# devkit_epet.net
KiCad netlist of a schematic drawn in EAGLE
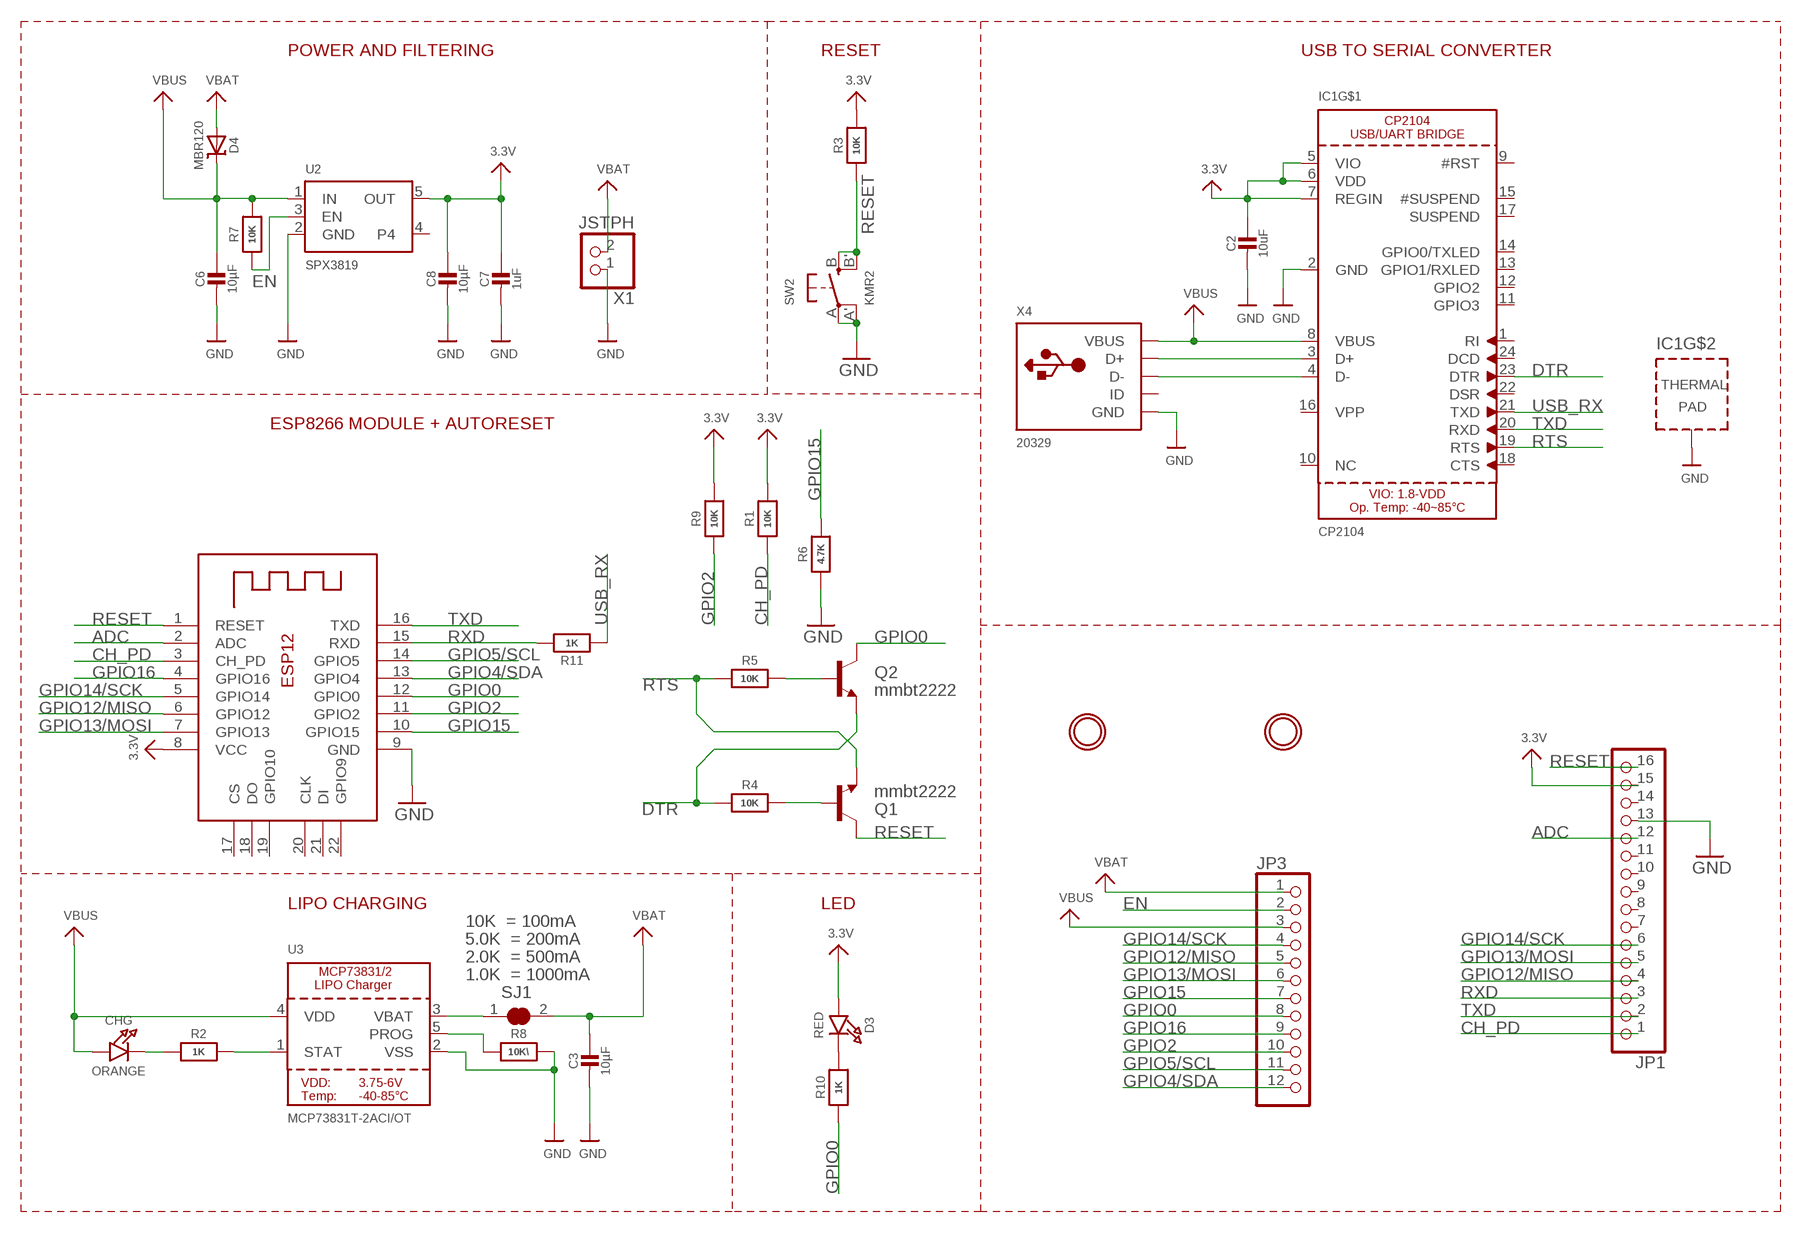
[diagram p0: schematic, sheet 1]

(export (version "E")
  (design (tool "Eeschema 10.0.6"))
  (components
    (comp (ref "C2")
      (value "10uF")
      (footprint "eagle-import:0805-NO")
      (libsource (lib "eagle-import") (part "CAP_CERAMIC0805-NOOUTLINE"))
    )
    (comp (ref "C3")
      (value "10µF")
      (footprint "eagle-import:0805-NO")
      (libsource (lib "eagle-import") (part "CAP_CERAMIC0805-NOOUTLINE"))
    )
    (comp (ref "C6")
      (value "10µF")
      (footprint "eagle-import:0805-NO")
      (libsource (lib "eagle-import") (part "CAP_CERAMIC0805-NOOUTLINE"))
    )
    (comp (ref "C7")
      (value "1uF")
      (footprint "eagle-import:0603-NO")
      (libsource (lib "eagle-import") (part "CAP_CERAMIC0603_NO"))
    )
    (comp (ref "C8")
      (value "10µF")
      (footprint "eagle-import:0805-NO")
      (libsource (lib "eagle-import") (part "CAP_CERAMIC0805-NOOUTLINE"))
    )
    (comp (ref "CHG")
      (value "ORANGE")
      (footprint "eagle-import:CHIPLED_0805_NOOUTLINE")
      (libsource (lib "eagle-import") (part "LED0805_NOOUTLINE"))
    )
    (comp (ref "D3")
      (value "RED")
      (footprint "eagle-import:CHIPLED_0805_NOOUTLINE")
      (libsource (lib "eagle-import") (part "LED0805_NOOUTLINE"))
    )
    (comp (ref "D4")
      (value "MBR120")
      (footprint "eagle-import:SOD-123")
      (libsource (lib "eagle-import") (part "DIODE-SCHOTTKYSOD-123"))
    )
    (comp (ref "IC1")
      (value "CP2104")
      (footprint "eagle-import:QFN24_4MM_SMSC")
      (libsource (lib "eagle-import") (part "CP2104"))
    )
    (comp (ref "JP1")
      (value "HEADER-1X16ROUND")
      (footprint "eagle-import:1X16_ROUND")
      (libsource (lib "eagle-import") (part "HEADER-1X16ROUND"))
    )
    (comp (ref "JP3")
      (value "HEADER-1X12")
      (footprint "eagle-import:1X12_ROUND")
      (libsource (lib "eagle-import") (part "HEADER-1X12"))
    )
    (comp (ref "Q1")
      (value "mmbt2222")
      (footprint "eagle-import:SOT23-3")
      (libsource (lib "eagle-import") (part "TRANSISTOR_NPNSOT23-3"))
    )
    (comp (ref "Q2")
      (value "mmbt2222")
      (footprint "eagle-import:SOT23-3")
      (libsource (lib "eagle-import") (part "TRANSISTOR_NPNSOT23-3"))
    )
    (comp (ref "R1")
      (value "10K")
      (footprint "eagle-import:0603-NO")
      (libsource (lib "eagle-import") (part "RESISTOR_0603_NOOUT"))
    )
    (comp (ref "R2")
      (value "1K")
      (footprint "eagle-import:0603-NO")
      (libsource (lib "eagle-import") (part "RESISTOR_0603_NOOUT"))
    )
    (comp (ref "R3")
      (value "10K")
      (footprint "eagle-import:0603-NO")
      (libsource (lib "eagle-import") (part "RESISTOR_0603_NOOUT"))
    )
    (comp (ref "R4")
      (value "10K")
      (footprint "eagle-import:0603-NO")
      (libsource (lib "eagle-import") (part "RESISTOR_0603_NOOUT"))
    )
    (comp (ref "R5")
      (value "10K")
      (footprint "eagle-import:_0603MP")
      (libsource (lib "eagle-import") (part "RESISTOR_0603MP"))
    )
    (comp (ref "R6")
      (value "4.7K")
      (footprint "eagle-import:0603-NO")
      (libsource (lib "eagle-import") (part "RESISTOR_0603_NOOUT"))
    )
    (comp (ref "R7")
      (value "10K")
      (footprint "eagle-import:0603-NO")
      (libsource (lib "eagle-import") (part "RESISTOR_0603_NOOUT"))
    )
    (comp (ref "R8")
      (value "10K\\")
      (footprint "eagle-import:0603-NO")
      (libsource (lib "eagle-import") (part "RESISTOR_0603_NOOUT"))
    )
    (comp (ref "R9")
      (value "10K")
      (footprint "eagle-import:0603-NO")
      (libsource (lib "eagle-import") (part "RESISTOR_0603_NOOUT"))
    )
    (comp (ref "R10")
      (value "1K")
      (footprint "eagle-import:0603-NO")
      (libsource (lib "eagle-import") (part "RESISTOR_0603_NOOUT"))
    )
    (comp (ref "R11")
      (value "1K")
      (footprint "eagle-import:_0603MP")
      (libsource (lib "eagle-import") (part "RESISTOR_0603MP"))
    )
    (comp (ref "SJ1")
      (value "SOLDERJUMPER_CLOSED")
      (footprint "eagle-import:SOLDERJUMPER_CLOSEDWIRE")
      (libsource (lib "eagle-import") (part "SOLDERJUMPER_CLOSED"))
    )
    (comp (ref "SW2")
      (value "KMR2")
      (footprint "eagle-import:BTN_KMR2_4.6X2.8")
      (libsource (lib "eagle-import") (part "SWITCH_TACT_SMT4.6X2.8"))
    )
    (comp (ref "U$31")
      (value "MOUNTINGHOLE2.5")
      (footprint "eagle-import:MOUNTINGHOLE_2.5_PLATED")
      (libsource (lib "eagle-import") (part "MOUNTINGHOLE2.5"))
    )
    (comp (ref "U$32")
      (value "MOUNTINGHOLE2.5")
      (footprint "eagle-import:MOUNTINGHOLE_2.5_PLATED")
      (libsource (lib "eagle-import") (part "MOUNTINGHOLE2.5"))
    )
    (comp (ref "U2")
      (value "SPX3819")
      (footprint "eagle-import:SOT23-5")
      (libsource (lib "eagle-import") (part "VREG_SOT23-5"))
    )
    (comp (ref "U3")
      (value "MCP73831T-2ACI/OT")
      (footprint "eagle-import:SOT23-5")
      (libsource (lib "eagle-import") (part "MCP73831/2"))
    )
    (comp (ref "X1")
      (value "JSTPH")
      (footprint "eagle-import:JSTPH2")
      (libsource (lib "eagle-import") (part "CON_JST_PH_2PIN"))
    )
    (comp (ref "X2")
      (value "ESP-12")
      (footprint "eagle-import:ESP-12E")
      (libsource (lib "eagle-import") (part "ESP-12E"))
    )
    (comp (ref "X4")
      (value "20329")
      (footprint "eagle-import:4UCONN_20329_V2")
      (libsource (lib "eagle-import") (part "USB_MICRO_20329_V2"))
    )
  )
  (nets
    (net (code "1") (name "/ADC") (class "Default")
      (node (ref "JP1") (pin "12") (pinfunction "12_12") (pintype "passive"))
      (node (ref "X2") (pin "2") (pinfunction "ADC_2") (pintype "passive"))
    )
    (net (code "2") (name "/CH_PD") (class "Default")
      (node (ref "JP1") (pin "1") (pinfunction "1_1") (pintype "passive"))
      (node (ref "R1") (pin "1") (pinfunction "1_1") (pintype "passive"))
      (node (ref "X2") (pin "3") (pinfunction "CH_PD_3") (pintype "input"))
    )
    (net (code "3") (name "/DTR") (class "Default")
      (node (ref "IC1") (pin "23") (pinfunction "DTR_23") (pintype "output"))
      (node (ref "Q2") (pin "2") (pinfunction "E_2") (pintype "passive"))
      (node (ref "R4") (pin "1") (pinfunction "1_1") (pintype "passive"))
    )
    (net (code "4") (name "/EN") (class "Default")
      (node (ref "JP3") (pin "2") (pinfunction "2_2") (pintype "passive"))
      (node (ref "R7") (pin "1") (pinfunction "1_1") (pintype "passive"))
      (node (ref "U2") (pin "3") (pinfunction "EN_3") (pintype "input"))
    )
    (net (code "5") (name "/GPIO0") (class "Default")
      (node (ref "JP3") (pin "8") (pinfunction "8_8") (pintype "passive"))
      (node (ref "Q2") (pin "3") (pinfunction "C_3") (pintype "passive"))
      (node (ref "R10") (pin "1") (pinfunction "1_1") (pintype "passive"))
      (node (ref "X2") (pin "12") (pinfunction "GPIO0_12") (pintype "bidirectional"))
    )
    (net (code "6") (name "/GPIO2") (class "Default")
      (node (ref "JP3") (pin "10") (pinfunction "10_10") (pintype "passive"))
      (node (ref "R9") (pin "1") (pinfunction "1_1") (pintype "passive"))
      (node (ref "X2") (pin "11") (pinfunction "GPIO2_11") (pintype "bidirectional"))
    )
    (net (code "7") (name "/GPIO4{slash}SDA") (class "Default")
      (node (ref "JP3") (pin "12") (pinfunction "12_12") (pintype "passive"))
      (node (ref "X2") (pin "13") (pinfunction "GPIO4_13") (pintype "bidirectional"))
    )
    (net (code "8") (name "/GPIO5{slash}SCL") (class "Default")
      (node (ref "JP3") (pin "11") (pinfunction "11_11") (pintype "passive"))
      (node (ref "X2") (pin "14") (pinfunction "GPIO5_14") (pintype "bidirectional"))
    )
    (net (code "9") (name "/GPIO12{slash}MISO") (class "Default")
      (node (ref "JP1") (pin "4") (pinfunction "4_4") (pintype "passive"))
      (node (ref "JP3") (pin "5") (pinfunction "5_5") (pintype "passive"))
      (node (ref "X2") (pin "6") (pinfunction "GPIO12_6") (pintype "bidirectional"))
    )
    (net (code "10") (name "/GPIO13{slash}MOSI") (class "Default")
      (node (ref "JP1") (pin "5") (pinfunction "5_5") (pintype "passive"))
      (node (ref "JP3") (pin "6") (pinfunction "6_6") (pintype "passive"))
      (node (ref "X2") (pin "7") (pinfunction "GPIO13_7") (pintype "bidirectional"))
    )
    (net (code "11") (name "/GPIO14{slash}SCK") (class "Default")
      (node (ref "JP1") (pin "6") (pinfunction "6_6") (pintype "passive"))
      (node (ref "JP3") (pin "4") (pinfunction "4_4") (pintype "passive"))
      (node (ref "X2") (pin "5") (pinfunction "GPIO14_5") (pintype "bidirectional"))
    )
    (net (code "12") (name "/GPIO15") (class "Default")
      (node (ref "JP3") (pin "7") (pinfunction "7_7") (pintype "passive"))
      (node (ref "R6") (pin "2") (pinfunction "2_2") (pintype "passive"))
      (node (ref "X2") (pin "10") (pinfunction "GPIO15_10") (pintype "bidirectional"))
    )
    (net (code "13") (name "/GPIO16") (class "Default")
      (node (ref "JP3") (pin "9") (pinfunction "9_9") (pintype "passive"))
      (node (ref "X2") (pin "4") (pinfunction "GPIO16_4") (pintype "bidirectional"))
    )
    (net (code "14") (name "/RESET") (class "Default")
      (node (ref "JP1") (pin "16") (pinfunction "16_16") (pintype "passive"))
      (node (ref "Q1") (pin "3") (pinfunction "C_3") (pintype "passive"))
      (node (ref "R3") (pin "1") (pinfunction "1_1") (pintype "passive"))
      (node (ref "SW2") (pin "B") (pinfunction "S_B") (pintype "passive"))
      (node (ref "SW2") (pin "B'") (pinfunction "S1_B'") (pintype "passive"))
      (node (ref "X2") (pin "1") (pinfunction "RESET_1") (pintype "input"))
    )
    (net (code "15") (name "/RTS") (class "Default")
      (node (ref "IC1") (pin "19") (pinfunction "RTS_19") (pintype "output"))
      (node (ref "Q1") (pin "2") (pinfunction "E_2") (pintype "passive"))
      (node (ref "R5") (pin "1") (pinfunction "1_1") (pintype "passive"))
    )
    (net (code "16") (name "/RXD") (class "Default")
      (node (ref "JP1") (pin "3") (pinfunction "3_3") (pintype "passive"))
      (node (ref "R11") (pin "2") (pinfunction "2_2") (pintype "passive"))
      (node (ref "X2") (pin "15") (pinfunction "RXD_15") (pintype "input"))
    )
    (net (code "17") (name "/TXD") (class "Default")
      (node (ref "IC1") (pin "20") (pinfunction "RXD_20") (pintype "input"))
      (node (ref "JP1") (pin "2") (pinfunction "2_2") (pintype "passive"))
      (node (ref "X2") (pin "16") (pinfunction "TXD_16") (pintype "output"))
    )
    (net (code "18") (name "/USB_RX") (class "Default")
      (node (ref "IC1") (pin "21") (pinfunction "TXD_21") (pintype "output"))
      (node (ref "R11") (pin "1") (pinfunction "1_1") (pintype "passive"))
    )
    (net (code "19") (name "3.3V") (class "Default")
      (node (ref "C2") (pin "1") (pinfunction "1_1") (pintype "passive"))
      (node (ref "C7") (pin "1") (pinfunction "1_1") (pintype "passive"))
      (node (ref "C8") (pin "1") (pinfunction "1_1") (pintype "passive"))
      (node (ref "D3") (pin "A") (pinfunction "A_A") (pintype "passive"))
      (node (ref "IC1") (pin "5") (pinfunction "VIO_5") (pintype "power_in"))
      (node (ref "IC1") (pin "6") (pinfunction "VDD_6") (pintype "power_in"))
      (node (ref "IC1") (pin "7") (pinfunction "REGIN_7") (pintype "power_in"))
      (node (ref "JP1") (pin "15") (pinfunction "15_15") (pintype "passive"))
      (node (ref "R1") (pin "2") (pinfunction "2_2") (pintype "passive"))
      (node (ref "R3") (pin "2") (pinfunction "2_2") (pintype "passive"))
      (node (ref "R9") (pin "2") (pinfunction "2_2") (pintype "passive"))
      (node (ref "U2") (pin "5") (pinfunction "OUT_5") (pintype "power_in"))
      (node (ref "X2") (pin "8") (pinfunction "VCC_8") (pintype "power_in"))
    )
    (net (code "20") (name "GND") (class "Default")
      (node (ref "C2") (pin "2") (pinfunction "2_2") (pintype "passive"))
      (node (ref "C3") (pin "2") (pinfunction "2_2") (pintype "passive"))
      (node (ref "C6") (pin "2") (pinfunction "2_2") (pintype "passive"))
      (node (ref "C7") (pin "2") (pinfunction "2_2") (pintype "passive"))
      (node (ref "C8") (pin "2") (pinfunction "2_2") (pintype "passive"))
      (node (ref "IC1") (pin "2") (pinfunction "GND_2") (pintype "power_in"))
      (node (ref "IC1") (pin "THERM") (pinfunction "TP_THERM") (pintype "power_in"))
      (node (ref "JP1") (pin "13") (pinfunction "13_13") (pintype "passive"))
      (node (ref "R6") (pin "1") (pinfunction "1_1") (pintype "passive"))
      (node (ref "R8") (pin "2") (pinfunction "2_2") (pintype "passive"))
      (node (ref "SW2") (pin "A") (pinfunction "P_A") (pintype "passive"))
      (node (ref "SW2") (pin "A'") (pinfunction "P1_A'") (pintype "passive"))
      (node (ref "U2") (pin "2") (pinfunction "GND_2") (pintype "power_in"))
      (node (ref "U3") (pin "2") (pinfunction "VSS_2") (pintype "power_in"))
      (node (ref "X1") (pin "1") (pinfunction "1_1") (pintype "passive"))
      (node (ref "X2") (pin "9") (pinfunction "GND_9") (pintype "power_in"))
      (node (ref "X4") (pin "BASE@1") (pinfunction "GND_BASE@1") (pintype "power_in"))
      (node (ref "X4") (pin "BASE@2") (pinfunction "GND_BASE@2") (pintype "power_in"))
      (node (ref "X4") (pin "GND") (pinfunction "GND_GND") (pintype "power_in"))
      (node (ref "X4") (pin "SPRT@1") (pinfunction "GND_SPRT@1") (pintype "power_in"))
      (node (ref "X4") (pin "SPRT@2") (pinfunction "GND_SPRT@2") (pintype "power_in"))
      (node (ref "X4") (pin "SPRT@3") (pinfunction "GND_SPRT@3") (pintype "power_in"))
      (node (ref "X4") (pin "SPRT@4") (pinfunction "GND_SPRT@4") (pintype "power_in"))
    )
    (net (code "21") (name "Net-(CHG-PadC)") (class "Default")
      (node (ref "CHG") (pin "C") (pinfunction "C_C") (pintype "passive"))
      (node (ref "R2") (pin "1") (pinfunction "1_1") (pintype "passive"))
    )
    (net (code "22") (name "Net-(D3-PadC)") (class "Default")
      (node (ref "D3") (pin "C") (pinfunction "C_C") (pintype "passive"))
      (node (ref "R10") (pin "2") (pinfunction "2_2") (pintype "passive"))
    )
    (net (code "23") (name "Net-(IC1A-D+)") (class "Default")
      (node (ref "IC1") (pin "3") (pinfunction "D+_3") (pintype "bidirectional"))
      (node (ref "X4") (pin "D+") (pinfunction "D+_D+") (pintype "bidirectional"))
    )
    (net (code "24") (name "Net-(IC1A-D-)") (class "Default")
      (node (ref "IC1") (pin "4") (pinfunction "D-_4") (pintype "bidirectional"))
      (node (ref "X4") (pin "D-") (pinfunction "D-_D-") (pintype "bidirectional"))
    )
    (net (code "25") (name "Net-(Q1-B)") (class "Default")
      (node (ref "Q1") (pin "1") (pinfunction "B_1") (pintype "passive"))
      (node (ref "R4") (pin "2") (pinfunction "2_2") (pintype "passive"))
    )
    (net (code "26") (name "Net-(Q2-B)") (class "Default")
      (node (ref "Q2") (pin "1") (pinfunction "B_1") (pintype "passive"))
      (node (ref "R5") (pin "2") (pinfunction "2_2") (pintype "passive"))
    )
    (net (code "27") (name "Net-(U3-PROG)") (class "Default")
      (node (ref "R8") (pin "1") (pinfunction "1_1") (pintype "passive"))
      (node (ref "U3") (pin "5") (pinfunction "PROG_5") (pintype "input"))
    )
    (net (code "28") (name "Net-(U3-STAT)") (class "Default")
      (node (ref "R2") (pin "2") (pinfunction "2_2") (pintype "passive"))
      (node (ref "U3") (pin "1") (pinfunction "STAT_1") (pintype "output"))
    )
    (net (code "29") (name "Net-(U3-VBAT)") (class "Default")
      (node (ref "SJ1") (pin "1") (pinfunction "1_1") (pintype "passive"))
      (node (ref "U3") (pin "3") (pinfunction "VBAT_3") (pintype "power_in"))
    )
    (net (code "30") (name "VBAT") (class "Default")
      (node (ref "C3") (pin "1") (pinfunction "1_1") (pintype "passive"))
      (node (ref "D4") (pin "A") (pinfunction "A_A") (pintype "passive"))
      (node (ref "JP3") (pin "1") (pinfunction "1_1") (pintype "passive"))
      (node (ref "SJ1") (pin "2") (pinfunction "2_2") (pintype "passive"))
      (node (ref "X1") (pin "2") (pinfunction "2_2") (pintype "passive"))
    )
    (net (code "31") (name "VBUS") (class "Default")
      (node (ref "C6") (pin "1") (pinfunction "1_1") (pintype "passive"))
      (node (ref "CHG") (pin "A") (pinfunction "A_A") (pintype "passive"))
      (node (ref "D4") (pin "C") (pinfunction "C_C") (pintype "passive"))
      (node (ref "IC1") (pin "8") (pinfunction "VBUS_8") (pintype "power_in"))
      (node (ref "JP3") (pin "3") (pinfunction "3_3") (pintype "passive"))
      (node (ref "R7") (pin "2") (pinfunction "2_2") (pintype "passive"))
      (node (ref "U2") (pin "1") (pinfunction "IN_1") (pintype "power_in"))
      (node (ref "U3") (pin "4") (pinfunction "VDD_4") (pintype "power_in"))
      (node (ref "X4") (pin "VBUS") (pinfunction "VBUS_VBUS") (pintype "power_in"))
    )
    (net (code "32") (name "unconnected-(IC1A-#RST-Pad9)") (class "Default")
      (node (ref "IC1") (pin "9") (pinfunction "#RST_9") (pintype "bidirectional"))
    )
    (net (code "33") (name "unconnected-(IC1A-#SUSPEND-Pad15)") (class "Default")
      (node (ref "IC1") (pin "15") (pinfunction "#SUSPEND_15") (pintype "output"))
    )
    (net (code "34") (name "unconnected-(IC1A-CTS-Pad18)") (class "Default")
      (node (ref "IC1") (pin "18") (pinfunction "CTS_18") (pintype "input"))
    )
    (net (code "35") (name "unconnected-(IC1A-DCD-Pad24)") (class "Default")
      (node (ref "IC1") (pin "24") (pinfunction "DCD_24") (pintype "input"))
    )
    (net (code "36") (name "unconnected-(IC1A-DSR-Pad22)") (class "Default")
      (node (ref "IC1") (pin "22") (pinfunction "DSR_22") (pintype "input"))
    )
    (net (code "37") (name "unconnected-(IC1A-GPIO0{slash}TXLED-Pad14)") (class "Default")
      (node (ref "IC1") (pin "14") (pinfunction "GPIO0/TXLED_14") (pintype "bidirectional"))
    )
    (net (code "38") (name "unconnected-(IC1A-GPIO1{slash}RXLED-Pad13)") (class "Default")
      (node (ref "IC1") (pin "13") (pinfunction "GPIO1/RXLED_13") (pintype "bidirectional"))
    )
    (net (code "39") (name "unconnected-(IC1A-GPIO2-Pad12)") (class "Default")
      (node (ref "IC1") (pin "12") (pinfunction "GPIO2_12") (pintype "bidirectional"))
    )
    (net (code "40") (name "unconnected-(IC1A-GPIO3-Pad11)") (class "Default")
      (node (ref "IC1") (pin "11") (pinfunction "GPIO3_11") (pintype "bidirectional"))
    )
    (net (code "41") (name "unconnected-(IC1A-NC-Pad10)") (class "Default")
      (node (ref "IC1") (pin "10") (pinfunction "NC_10") (pintype "no_connect"))
    )
    (net (code "42") (name "unconnected-(IC1A-RI-Pad1)") (class "Default")
      (node (ref "IC1") (pin "1") (pinfunction "RI_1") (pintype "input"))
    )
    (net (code "43") (name "unconnected-(IC1A-SUSPEND-Pad17)") (class "Default")
      (node (ref "IC1") (pin "17") (pinfunction "SUSPEND_17") (pintype "output"))
    )
    (net (code "44") (name "unconnected-(IC1A-VPP-Pad16)") (class "Default")
      (node (ref "IC1") (pin "16") (pinfunction "VPP_16") (pintype "bidirectional"))
    )
    (net (code "45") (name "unconnected-(JP1-Pad7)") (class "Default")
      (node (ref "JP1") (pin "7") (pinfunction "7_7") (pintype "passive"))
    )
    (net (code "46") (name "unconnected-(JP1-Pad8)") (class "Default")
      (node (ref "JP1") (pin "8") (pinfunction "8_8") (pintype "passive"))
    )
    (net (code "47") (name "unconnected-(JP1-Pad9)") (class "Default")
      (node (ref "JP1") (pin "9") (pinfunction "9_9") (pintype "passive"))
    )
    (net (code "48") (name "unconnected-(JP1-Pad10)") (class "Default")
      (node (ref "JP1") (pin "10") (pinfunction "10_10") (pintype "passive"))
    )
    (net (code "49") (name "unconnected-(JP1-Pad11)") (class "Default")
      (node (ref "JP1") (pin "11") (pinfunction "11_11") (pintype "passive"))
    )
    (net (code "50") (name "unconnected-(JP1-Pad14)") (class "Default")
      (node (ref "JP1") (pin "14") (pinfunction "14_14") (pintype "passive"))
    )
    (net (code "51") (name "unconnected-(U2-P4-Pad4)") (class "Default")
      (node (ref "U2") (pin "4") (pinfunction "P4_4") (pintype "bidirectional"))
    )
    (net (code "52") (name "unconnected-(X2-CLK-Pad20)") (class "Default")
      (node (ref "X2") (pin "20") (pinfunction "CLK_20") (pintype "bidirectional"))
    )
    (net (code "53") (name "unconnected-(X2-CS-Pad17)") (class "Default")
      (node (ref "X2") (pin "17") (pinfunction "CS_17") (pintype "bidirectional"))
    )
    (net (code "54") (name "unconnected-(X2-DI-Pad21)") (class "Default")
      (node (ref "X2") (pin "21") (pinfunction "DI_21") (pintype "bidirectional"))
    )
    (net (code "55") (name "unconnected-(X2-DO-Pad18)") (class "Default")
      (node (ref "X2") (pin "18") (pinfunction "DO_18") (pintype "bidirectional"))
    )
    (net (code "56") (name "unconnected-(X2-GPIO9-Pad22)") (class "Default")
      (node (ref "X2") (pin "22") (pinfunction "GPIO9_22") (pintype "bidirectional"))
    )
    (net (code "57") (name "unconnected-(X2-GPIO10-Pad19)") (class "Default")
      (node (ref "X2") (pin "19") (pinfunction "GPIO10_19") (pintype "bidirectional"))
    )
    (net (code "58") (name "unconnected-(X4-PadID)") (class "Default")
      (node (ref "X4") (pin "ID") (pinfunction "ID_ID") (pintype "bidirectional"))
    )
  )
)
